# POWER_RAIL.net
KiCad netlist of a schematic drawn in Altium Designer
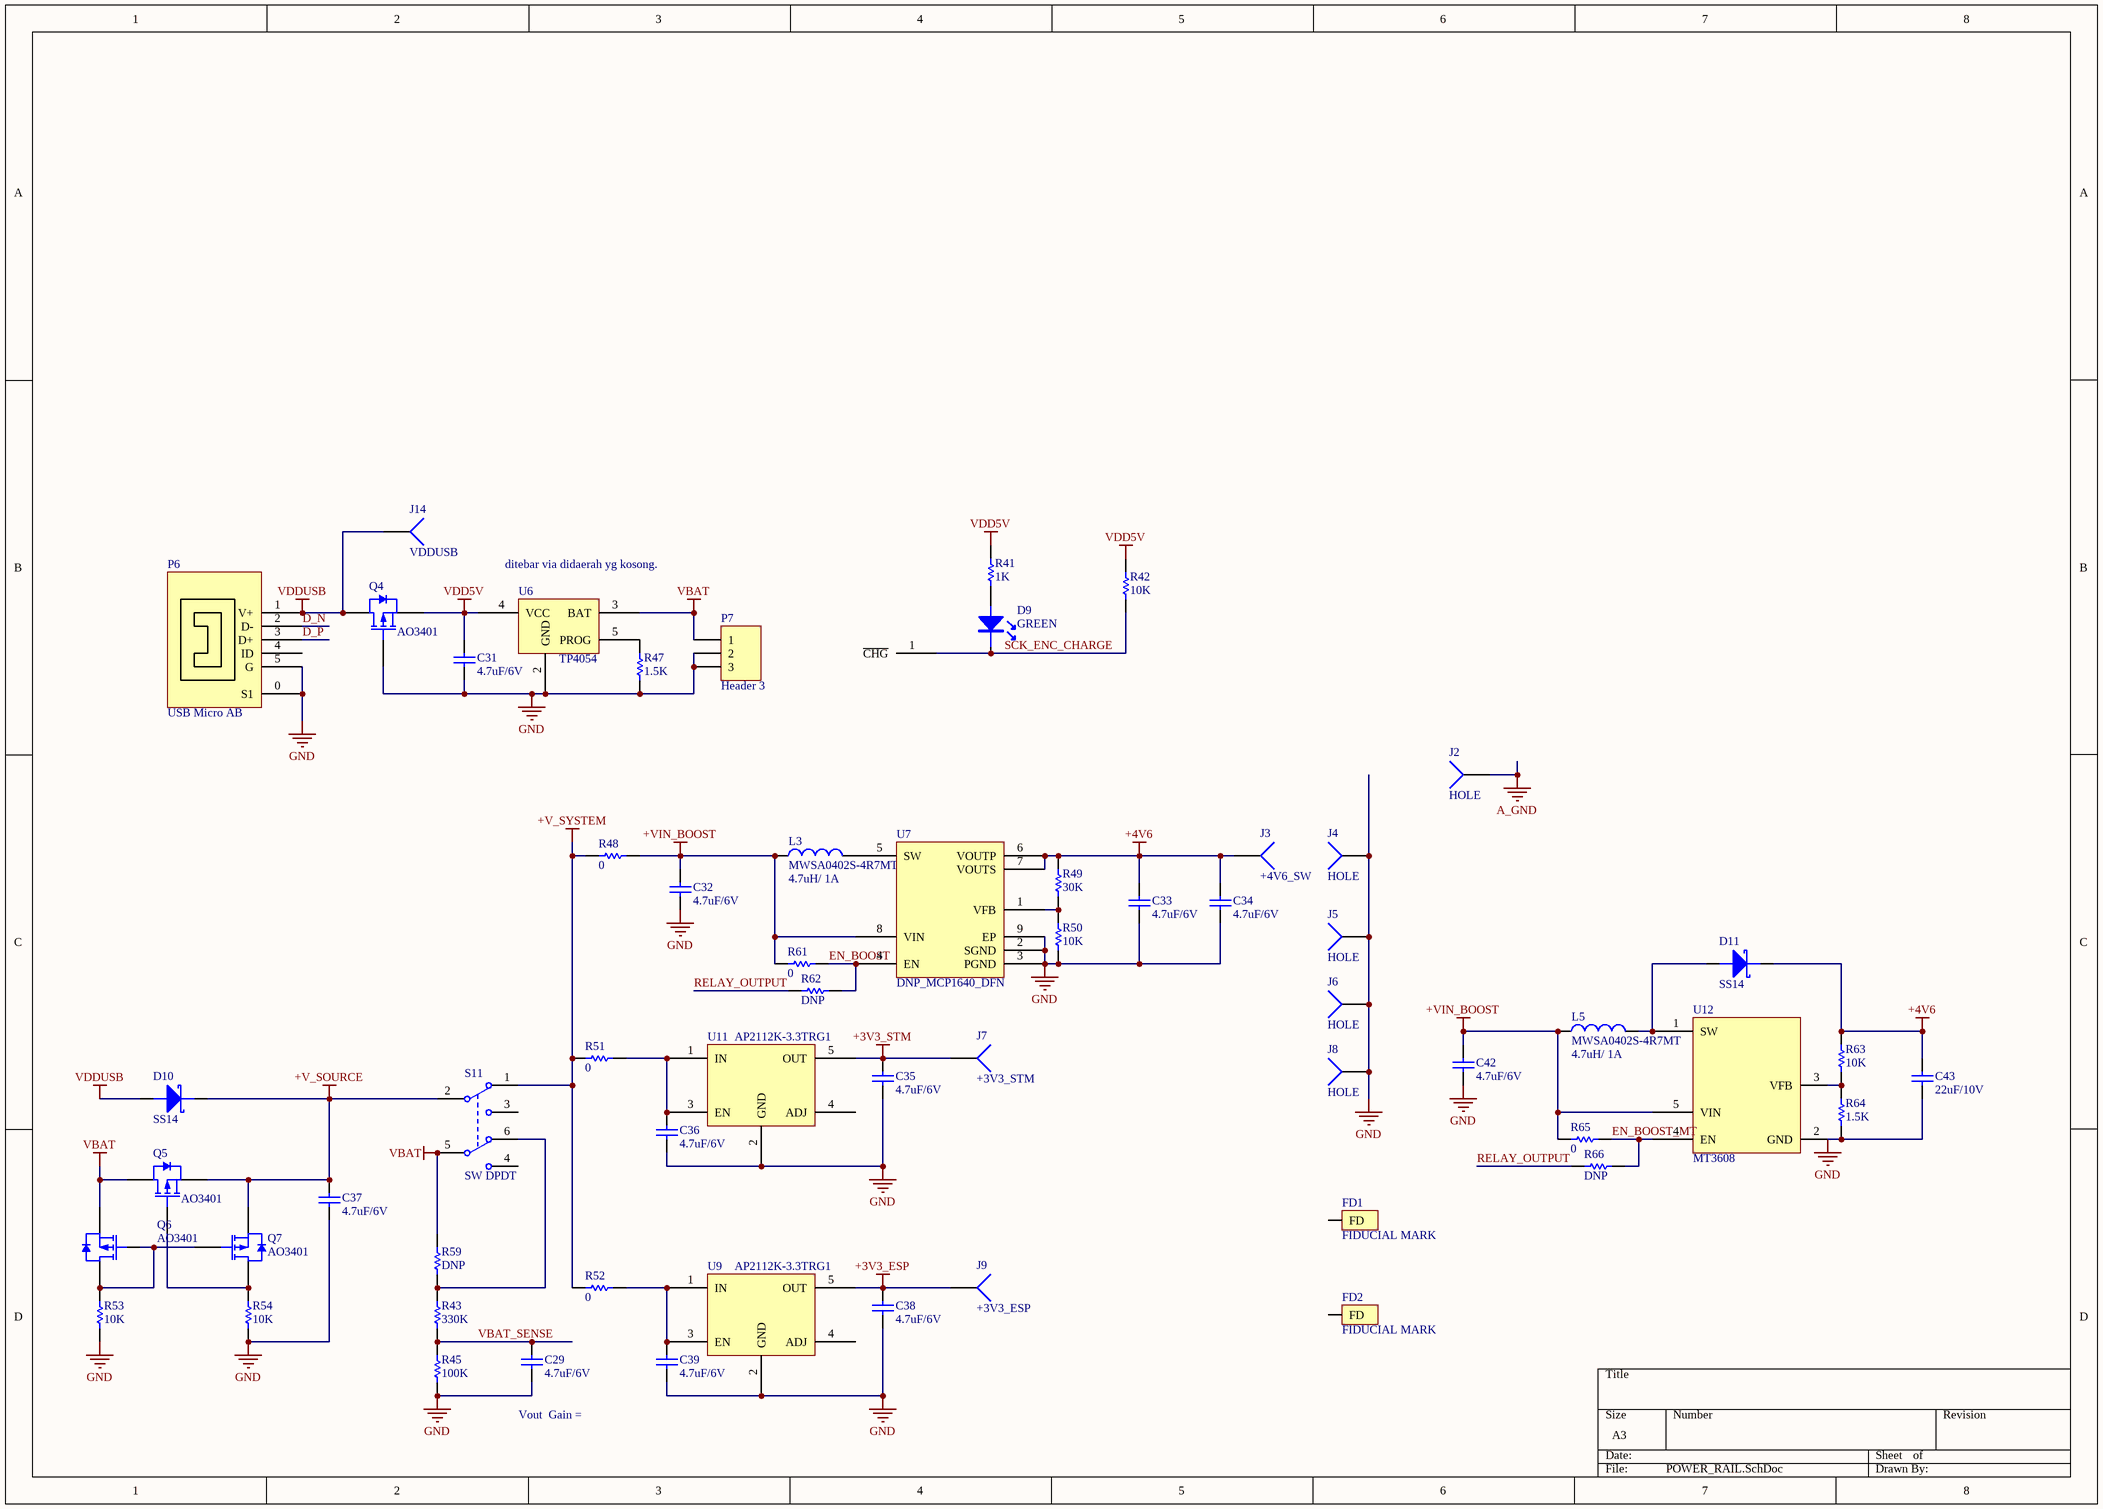
[diagram p0: POWER_RAIL.SchDoc]

(export (version "E")
  (design (tool "Eeschema 10.0.6"))
  (components
    (comp (ref "C29")
      (value "4.7uF/6V")
      (footprint "CR2012-0805")
      (description "Capacitor (Semiconductor SIM Model)")
      (fields (field (name "PUBLISHER") "Altium Limited"))
      (libsource (lib "passive") (part "Cap Semi"))
    )
    (comp (ref "C31")
      (value "4.7uF/6V")
      (footprint "CR2012-0805")
      (description "Capacitor (Semiconductor SIM Model)")
      (fields (field (name "PUBLISHER") "Altium Limited"))
      (libsource (lib "passive") (part "Cap Semi"))
    )
    (comp (ref "C32")
      (value "4.7uF/6V")
      (footprint "CR2012-0805")
      (description "Capacitor (Semiconductor SIM Model)")
      (fields (field (name "PUBLISHER") "Altium Limited"))
      (libsource (lib "passive") (part "Cap Semi"))
    )
    (comp (ref "C33")
      (value "4.7uF/6V")
      (footprint "CR2012-0805")
      (description "Capacitor (Semiconductor SIM Model)")
      (fields (field (name "PUBLISHER") "Altium Limited"))
      (libsource (lib "passive") (part "Cap Semi"))
    )
    (comp (ref "C34")
      (value "4.7uF/6V")
      (footprint "CR2012-0805")
      (description "Capacitor (Semiconductor SIM Model)")
      (fields (field (name "PUBLISHER") "Altium Limited"))
      (libsource (lib "passive") (part "Cap Semi"))
    )
    (comp (ref "C35")
      (value "4.7uF/6V")
      (footprint "CR2012-0805")
      (description "Capacitor (Semiconductor SIM Model)")
      (fields (field (name "PUBLISHER") "Altium Limited"))
      (libsource (lib "passive") (part "Cap Semi"))
    )
    (comp (ref "C36")
      (value "4.7uF/6V")
      (footprint "CR2012-0805")
      (description "Capacitor (Semiconductor SIM Model)")
      (fields (field (name "PUBLISHER") "Altium Limited"))
      (libsource (lib "passive") (part "Cap Semi"))
    )
    (comp (ref "C37")
      (value "4.7uF/6V")
      (footprint "CR2012-0805")
      (description "Capacitor (Semiconductor SIM Model)")
      (fields (field (name "PUBLISHER") "Altium Limited"))
      (libsource (lib "passive") (part "Cap Semi"))
    )
    (comp (ref "C38")
      (value "4.7uF/6V")
      (footprint "CR2012-0805")
      (description "Capacitor (Semiconductor SIM Model)")
      (fields (field (name "PUBLISHER") "Altium Limited"))
      (libsource (lib "passive") (part "Cap Semi"))
    )
    (comp (ref "C39")
      (value "4.7uF/6V")
      (footprint "CR2012-0805")
      (description "Capacitor (Semiconductor SIM Model)")
      (fields (field (name "PUBLISHER") "Altium Limited"))
      (libsource (lib "passive") (part "Cap Semi"))
    )
    (comp (ref "C42")
      (value "4.7uF/6V")
      (footprint "CR2012-0805")
      (description "Capacitor (Semiconductor SIM Model)")
      (fields (field (name "PUBLISHER") "Altium Limited"))
      (libsource (lib "passive") (part "Cap Semi"))
    )
    (comp (ref "C43")
      (value "22uF/10V")
      (footprint "CR3216-1206")
      (description "Capacitor (Semiconductor SIM Model)")
      (fields (field (name "PUBLISHER") "Altium Limited"))
      (libsource (lib "passive") (part "Cap Semi"))
    )
    (comp (ref "D9")
      (value "GREEN")
      (footprint "LED1206")
      (description "SMT LED")
      (libsource (lib "Vowstar_Basic_Device") (part "SMT_LED_0603"))
    )
    (comp (ref "D10")
      (value "SS14")
      (footprint "DO-214AC (SMA)")
      (description "Schottky Barrier Diodes")
      (fields (field (name "MANUFACTURER PART NUMBER") "SS18"))
      (libsource (lib "H2SCHALTIUM") (part "DIODE SCHOTTKY"))
    )
    (comp (ref "D11")
      (value "SS14")
      (footprint "DO-214AC (SMA)")
      (description "Schottky Barrier Diodes")
      (fields (field (name "MANUFACTURER PART NUMBER") "SS18"))
      (libsource (lib "H2SCHALTIUM") (part "DIODE SCHOTTKY"))
    )
    (comp (ref "FD1")
      (value "FIDUCIAL MARK")
      (footprint "FIDU-ROUND")
      (description "0.5mm fiducial marking with 1mm solder expansion")
      (libsource (lib "passive") (part "FIDU"))
    )
    (comp (ref "FD2")
      (value "FIDUCIAL MARK")
      (footprint "FIDU-ROUND")
      (description "0.5mm fiducial marking with 1mm solder expansion")
      (libsource (lib "passive") (part "FIDU"))
    )
    (comp (ref "J2")
      (value "HOLE")
      (footprint "HOLE_45MM")
      (description "Socket")
      (fields (field (name "PUBLISHER") "Altium Limited"))
      (libsource (lib "Miscellaneous Connectors") (part "Socket"))
    )
    (comp (ref "J3")
      (value "+4V6_SW")
      (footprint "PIN1")
      (description "Socket")
      (fields (field (name "PUBLISHER") "Altium Limited"))
      (libsource (lib "Miscellaneous Connectors") (part "Socket"))
    )
    (comp (ref "J4")
      (value "HOLE")
      (footprint "HOLE_45MM")
      (description "Socket")
      (fields (field (name "PUBLISHER") "Altium Limited"))
      (libsource (lib "Miscellaneous Connectors") (part "Socket"))
    )
    (comp (ref "J5")
      (value "HOLE")
      (footprint "HOLE_45MM")
      (description "Socket")
      (fields (field (name "PUBLISHER") "Altium Limited"))
      (libsource (lib "Miscellaneous Connectors") (part "Socket"))
    )
    (comp (ref "J6")
      (value "HOLE")
      (footprint "HOLE_45MM")
      (description "Socket")
      (fields (field (name "PUBLISHER") "Altium Limited"))
      (libsource (lib "Miscellaneous Connectors") (part "Socket"))
    )
    (comp (ref "J7")
      (value "+3V3_STM")
      (footprint "PIN1")
      (description "Socket")
      (fields (field (name "PUBLISHER") "Altium Limited"))
      (libsource (lib "Miscellaneous Connectors") (part "Socket"))
    )
    (comp (ref "J8")
      (value "HOLE")
      (footprint "HOLE_45MM")
      (description "Socket")
      (fields (field (name "PUBLISHER") "Altium Limited"))
      (libsource (lib "Miscellaneous Connectors") (part "Socket"))
    )
    (comp (ref "J9")
      (value "+3V3_ESP")
      (footprint "PIN1")
      (description "Socket")
      (fields (field (name "PUBLISHER") "Altium Limited"))
      (libsource (lib "Miscellaneous Connectors") (part "Socket"))
    )
    (comp (ref "J14")
      (value "VDDUSB")
      (footprint "PIN1")
      (description "Socket")
      (fields (field (name "PUBLISHER") "Altium Limited"))
      (libsource (lib "Miscellaneous Connectors") (part "Socket"))
    )
    (comp (ref "L3")
      (value "MWSA0402S-4R7MT")
      (footprint "IND4X4MM")
      (description "Inductor")
      (fields (field (name "ALTIUM_VALUE") "4.7uH/ 1A") (field (name "PUBLISHER") "Altium Limited"))
      (libsource (lib "passive") (part "Inductor"))
    )
    (comp (ref "L5")
      (value "MWSA0402S-4R7MT")
      (footprint "IND4X4MM")
      (description "Inductor")
      (fields (field (name "ALTIUM_VALUE") "4.7uH/ 1A") (field (name "PUBLISHER") "Altium Limited"))
      (libsource (lib "passive") (part "Inductor"))
    )
    (comp (ref "P6")
      (value "USB Micro AB")
      (footprint "USB_MICRO_wi_LEG")
      (description "USB Micro AB connector")
      (libsource (lib "passive") (part "USB Micro AB"))
    )
    (comp (ref "P7")
      (value "Header 3")
      (footprint "Molex 3p Male")
      (description "Header, 3-Pin")
      (fields (field (name "PUBLISHER") "Altium Limited"))
      (libsource (lib "Miscellaneous Connectors") (part "Header 3"))
    )
    (comp (ref "Q4")
      (value "AO3401")
      (footprint "SOT-23-3")
      (description "30V P-Channel MOSFET")
      (fields (field (name "PUBLISHER") "Altium Limited"))
      (libsource (lib "passive") (part "AO3401"))
    )
    (comp (ref "Q5")
      (value "AO3401")
      (footprint "SOT-23-3")
      (description "30V P-Channel MOSFET")
      (fields (field (name "PUBLISHER") "Altium Limited"))
      (libsource (lib "passive") (part "AO3401"))
    )
    (comp (ref "Q6")
      (value "AO3401")
      (footprint "SOT-23-3")
      (description "30V P-Channel MOSFET")
      (fields (field (name "PUBLISHER") "Altium Limited"))
      (libsource (lib "passive") (part "AO3401"))
    )
    (comp (ref "Q7")
      (value "AO3401")
      (footprint "SOT-23-3")
      (description "30V P-Channel MOSFET")
      (fields (field (name "PUBLISHER") "Altium Limited"))
      (libsource (lib "passive") (part "AO3401"))
    )
    (comp (ref "R41")
      (value "1K")
      (footprint "CR2012-0805")
      (description "Semiconductor Resistor")
      (fields (field (name "PUBLISHER") "Altium Limited"))
      (libsource (lib "passive") (part "Res Semi"))
    )
    (comp (ref "R42")
      (value "10K")
      (footprint "CR2012-0805")
      (description "Semiconductor Resistor")
      (fields (field (name "PUBLISHER") "Altium Limited"))
      (libsource (lib "passive") (part "Res Semi"))
    )
    (comp (ref "R43")
      (value "330K")
      (footprint "CR2012-0805")
      (description "Semiconductor Resistor")
      (fields (field (name "PUBLISHER") "Altium Limited"))
      (libsource (lib "passive") (part "Res Semi"))
    )
    (comp (ref "R45")
      (value "100K")
      (footprint "CR2012-0805")
      (description "Semiconductor Resistor")
      (fields (field (name "PUBLISHER") "Altium Limited"))
      (libsource (lib "passive") (part "Res Semi"))
    )
    (comp (ref "R47")
      (value "1.5K")
      (footprint "CR2012-0805")
      (description "Semiconductor Resistor")
      (fields (field (name "PUBLISHER") "Altium Limited"))
      (libsource (lib "passive") (part "Res Semi"))
    )
    (comp (ref "R48")
      (value "0")
      (footprint "JP1_SMD")
      (description "Semiconductor Resistor")
      (fields (field (name "PUBLISHER") "Altium Limited"))
      (libsource (lib "passive") (part "Res Semi"))
    )
    (comp (ref "R49")
      (value "30K")
      (footprint "CR2012-0805")
      (description "Semiconductor Resistor")
      (fields (field (name "PUBLISHER") "Altium Limited"))
      (libsource (lib "passive") (part "Res Semi"))
    )
    (comp (ref "R50")
      (value "10K")
      (footprint "CR2012-0805")
      (description "Semiconductor Resistor")
      (fields (field (name "PUBLISHER") "Altium Limited"))
      (libsource (lib "passive") (part "Res Semi"))
    )
    (comp (ref "R51")
      (value "0")
      (footprint "JP1_SMD")
      (description "Semiconductor Resistor")
      (fields (field (name "PUBLISHER") "Altium Limited"))
      (libsource (lib "passive") (part "Res Semi"))
    )
    (comp (ref "R52")
      (value "0")
      (footprint "JP1_SMD")
      (description "Semiconductor Resistor")
      (fields (field (name "PUBLISHER") "Altium Limited"))
      (libsource (lib "passive") (part "Res Semi"))
    )
    (comp (ref "R53")
      (value "10K")
      (footprint "CR2012-0805")
      (description "Semiconductor Resistor")
      (fields (field (name "PUBLISHER") "Altium Limited"))
      (libsource (lib "passive") (part "Res Semi"))
    )
    (comp (ref "R54")
      (value "10K")
      (footprint "CR2012-0805")
      (description "Semiconductor Resistor")
      (fields (field (name "PUBLISHER") "Altium Limited"))
      (libsource (lib "passive") (part "Res Semi"))
    )
    (comp (ref "R59")
      (value "DNP")
      (footprint "JP1_SMD")
      (description "Semiconductor Resistor")
      (fields (field (name "PUBLISHER") "Altium Limited"))
      (libsource (lib "passive") (part "Res Semi"))
    )
    (comp (ref "R61")
      (value "0")
      (footprint "JP1_SMD")
      (description "Semiconductor Resistor")
      (fields (field (name "PUBLISHER") "Altium Limited"))
      (libsource (lib "passive") (part "Res Semi"))
    )
    (comp (ref "R62")
      (value "DNP")
      (footprint "JP1_SMD")
      (description "Semiconductor Resistor")
      (fields (field (name "PUBLISHER") "Altium Limited"))
      (libsource (lib "passive") (part "Res Semi"))
    )
    (comp (ref "R63")
      (value "10K")
      (footprint "CR2012-0805")
      (description "Semiconductor Resistor")
      (fields (field (name "PUBLISHER") "Altium Limited"))
      (libsource (lib "passive") (part "Res Semi"))
    )
    (comp (ref "R64")
      (value "1.5K")
      (footprint "CR2012-0805")
      (description "Semiconductor Resistor")
      (fields (field (name "PUBLISHER") "Altium Limited"))
      (libsource (lib "passive") (part "Res Semi"))
    )
    (comp (ref "R65")
      (value "0")
      (footprint "JP1_SMD")
      (description "Semiconductor Resistor")
      (fields (field (name "PUBLISHER") "Altium Limited"))
      (libsource (lib "passive") (part "Res Semi"))
    )
    (comp (ref "R66")
      (value "DNP")
      (footprint "JP1_SMD")
      (description "Semiconductor Resistor")
      (fields (field (name "PUBLISHER") "Altium Limited"))
      (libsource (lib "passive") (part "Res Semi"))
    )
    (comp (ref "S11")
      (value "SW DPDT")
      (footprint "SWITCH_SPDT")
      (description "Switch")
      (fields (field (name "PUBLISHER") "Altium Limited"))
      (libsource (lib "passive") (part "SW DPDT"))
    )
    (comp (ref "U6") (value "TP4054") (footprint "SOT23-5") (libsource (lib "TP4056") (part "TP4056")))
    (comp (ref "U7")
      (value "DNP_MCP1640_DFN")
      (footprint "DFN-8_2X3")
      (description "Synchronous Boost Regulator with True Output Disconnect or Input/Output Bypass Option")
      (libsource (lib "active") (part "MCP1640_DFN"))
    )
    (comp (ref "U9")
      (value "AP2112K-3.3TRG1")
      (footprint "SOT-23-5")
      (description "IC REG LDO ADJ .15A SOT25-5")
      (fields
        (field (name "MANUFACTURER") "Diodes Inc")
        (field (name "SUPPLIER PART NUMBER") "AP2112K-3.3TRG1")
        (field (name "MANUFACTURER PART NUMBER") "AP7311-18WG-7")
      )
      (libsource (lib "active") (part "AP7311"))
    )
    (comp (ref "U11")
      (value "AP2112K-3.3TRG1")
      (footprint "SOT-23-5")
      (description "IC REG LDO ADJ .15A SOT25-5")
      (fields
        (field (name "MANUFACTURER") "Diodes Inc")
        (field (name "SUPPLIER PART NUMBER") "AP2112K-3.3TRG1")
        (field (name "MANUFACTURER PART NUMBER") "AP7311-18WG-7")
      )
      (libsource (lib "active") (part "AP7311"))
    )
    (comp (ref "U12")
      (value "MT3608")
      (footprint "SOT-23-6")
      (description "Synchronous Boost Regulator with True Output Disconnect or Input/Output Bypass Option")
      (libsource (lib "active") (part "MT3608"))
    )
  )
  (nets
    (net (code "1") (name "+3V3_ESP") (class "Default")
      (node (ref "C38") (pin "2") (pinfunction "2_2") (pintype "passive"))
      (node (ref "J9") (pin "1") (pinfunction "1_1") (pintype "passive"))
      (node (ref "U9") (pin "5") (pinfunction "OUT_5") (pintype "passive"))
    )
    (net (code "2") (name "+3V3_STM") (class "Default")
      (node (ref "C35") (pin "2") (pinfunction "2_2") (pintype "passive"))
      (node (ref "J7") (pin "1") (pinfunction "1_1") (pintype "passive"))
      (node (ref "U11") (pin "5") (pinfunction "OUT_5") (pintype "passive"))
    )
    (net (code "3") (name "+4V6") (class "Default")
      (node (ref "C33") (pin "2") (pinfunction "2_2") (pintype "passive"))
      (node (ref "C34") (pin "2") (pinfunction "2_2") (pintype "passive"))
      (node (ref "C43") (pin "2") (pinfunction "2_2") (pintype "passive"))
      (node (ref "D11") (pin "2") (pinfunction "K_2") (pintype "passive"))
      (node (ref "J3") (pin "1") (pinfunction "1_1") (pintype "passive"))
      (node (ref "R49") (pin "2") (pinfunction "2_2") (pintype "passive"))
      (node (ref "R63") (pin "2") (pinfunction "2_2") (pintype "passive"))
      (node (ref "U7") (pin "6") (pinfunction "VOUTP_6") (pintype "passive"))
      (node (ref "U7") (pin "7") (pinfunction "VOUTS_7") (pintype "passive"))
    )
    (net (code "4") (name "+VIN_BOOST") (class "Default")
      (node (ref "C32") (pin "2") (pinfunction "2_2") (pintype "passive"))
      (node (ref "C42") (pin "2") (pinfunction "2_2") (pintype "passive"))
      (node (ref "L3") (pin "1") (pinfunction "1_1") (pintype "passive"))
      (node (ref "L5") (pin "1") (pinfunction "1_1") (pintype "passive"))
      (node (ref "R48") (pin "2") (pinfunction "2_2") (pintype "passive"))
      (node (ref "R61") (pin "1") (pinfunction "1_1") (pintype "passive"))
      (node (ref "R65") (pin "1") (pinfunction "1_1") (pintype "passive"))
      (node (ref "U12") (pin "5") (pinfunction "VIN_5") (pintype "passive"))
      (node (ref "U7") (pin "8") (pinfunction "VIN_8") (pintype "passive"))
    )
    (net (code "5") (name "+V_SOURCE") (class "Default")
      (node (ref "C37") (pin "2") (pinfunction "2_2") (pintype "passive"))
      (node (ref "D10") (pin "2") (pinfunction "K_2") (pintype "passive"))
      (node (ref "Q5") (pin "2") (pinfunction "S_2") (pintype "passive"))
      (node (ref "Q7") (pin "2") (pinfunction "S_2") (pintype "passive"))
      (node (ref "S11") (pin "2") (pinfunction "COMMON1_2") (pintype "passive"))
    )
    (net (code "6") (name "+V_SYSTEM") (class "Default")
      (node (ref "R48") (pin "1") (pinfunction "1_1") (pintype "passive"))
      (node (ref "R51") (pin "1") (pinfunction "1_1") (pintype "passive"))
      (node (ref "R52") (pin "1") (pinfunction "1_1") (pintype "passive"))
      (node (ref "S11") (pin "1") (pinfunction "NC1_1") (pintype "passive"))
    )
    (net (code "7") (name "/D_N") (class "Default")
      (node (ref "P6") (pin "2") (pinfunction "D-_2") (pintype "passive"))
    )
    (net (code "8") (name "/D_P") (class "Default")
      (node (ref "P6") (pin "3") (pinfunction "D+_3") (pintype "passive"))
    )
    (net (code "9") (name "/EN_BOOST") (class "Default")
      (node (ref "R61") (pin "2") (pinfunction "2_2") (pintype "passive"))
      (node (ref "R62") (pin "1") (pinfunction "1_1") (pintype "passive"))
      (node (ref "U7") (pin "4") (pinfunction "EN_4") (pintype "passive"))
    )
    (net (code "10") (name "/EN_BOOST_MT") (class "Default")
      (node (ref "R65") (pin "2") (pinfunction "2_2") (pintype "passive"))
      (node (ref "R66") (pin "1") (pinfunction "1_1") (pintype "passive"))
      (node (ref "U12") (pin "4") (pinfunction "EN_4") (pintype "passive"))
    )
    (net (code "11") (name "/RELAY_OUTPUT") (class "Default")
      (node (ref "R62") (pin "2") (pinfunction "2_2") (pintype "passive"))
      (node (ref "R66") (pin "2") (pinfunction "2_2") (pintype "passive"))
    )
    (net (code "12") (name "/SCK_ENC_CHARGE") (class "Default")
      (node (ref "D9") (pin "K") (pinfunction "K_K") (pintype "passive"))
      (node (ref "R42") (pin "1") (pinfunction "1_1") (pintype "passive"))
      (node (ref "U6") (pin "1") (pinfunction "~{CHG}_1") (pintype "passive"))
    )
    (net (code "13") (name "/VBAT_SENSE") (class "Default")
      (node (ref "C29") (pin "2") (pinfunction "2_2") (pintype "passive"))
      (node (ref "R43") (pin "1") (pinfunction "1_1") (pintype "passive"))
      (node (ref "R45") (pin "2") (pinfunction "2_2") (pintype "passive"))
    )
    (net (code "14") (name "A_GND") (class "Default")
      (node (ref "J2") (pin "1") (pinfunction "1_1") (pintype "passive"))
    )
    (net (code "15") (name "GND") (class "Default")
      (node (ref "C29") (pin "1") (pinfunction "1_1") (pintype "passive"))
      (node (ref "C31") (pin "1") (pinfunction "1_1") (pintype "passive"))
      (node (ref "C32") (pin "1") (pinfunction "1_1") (pintype "passive"))
      (node (ref "C33") (pin "1") (pinfunction "1_1") (pintype "passive"))
      (node (ref "C34") (pin "1") (pinfunction "1_1") (pintype "passive"))
      (node (ref "C35") (pin "1") (pinfunction "1_1") (pintype "passive"))
      (node (ref "C36") (pin "1") (pinfunction "1_1") (pintype "passive"))
      (node (ref "C37") (pin "1") (pinfunction "1_1") (pintype "passive"))
      (node (ref "C38") (pin "1") (pinfunction "1_1") (pintype "passive"))
      (node (ref "C39") (pin "1") (pinfunction "1_1") (pintype "passive"))
      (node (ref "C42") (pin "1") (pinfunction "1_1") (pintype "passive"))
      (node (ref "C43") (pin "1") (pinfunction "1_1") (pintype "passive"))
      (node (ref "J4") (pin "1") (pinfunction "1_1") (pintype "passive"))
      (node (ref "J5") (pin "1") (pinfunction "1_1") (pintype "passive"))
      (node (ref "J6") (pin "1") (pinfunction "1_1") (pintype "passive"))
      (node (ref "J8") (pin "1") (pinfunction "1_1") (pintype "passive"))
      (node (ref "P6") (pin "0") (pinfunction "S1_0") (pintype "passive"))
      (node (ref "P6") (pin "5") (pinfunction "G_5") (pintype "passive"))
      (node (ref "P7") (pin "2") (pinfunction "2_2") (pintype "passive"))
      (node (ref "P7") (pin "3") (pinfunction "3_3") (pintype "passive"))
      (node (ref "Q4") (pin "1") (pinfunction "G_1") (pintype "passive"))
      (node (ref "R45") (pin "1") (pinfunction "1_1") (pintype "passive"))
      (node (ref "R47") (pin "1") (pinfunction "1_1") (pintype "passive"))
      (node (ref "R50") (pin "1") (pinfunction "1_1") (pintype "passive"))
      (node (ref "R53") (pin "1") (pinfunction "1_1") (pintype "passive"))
      (node (ref "R54") (pin "1") (pinfunction "1_1") (pintype "passive"))
      (node (ref "R64") (pin "1") (pinfunction "1_1") (pintype "passive"))
      (node (ref "U11") (pin "2") (pinfunction "GND_2") (pintype "passive"))
      (node (ref "U12") (pin "2") (pinfunction "GND_2") (pintype "passive"))
      (node (ref "U6") (pin "2") (pinfunction "GND_2") (pintype "passive"))
      (node (ref "U7") (pin "2") (pinfunction "SGND_2") (pintype "passive"))
      (node (ref "U7") (pin "3") (pinfunction "PGND_3") (pintype "passive"))
      (node (ref "U7") (pin "9") (pinfunction "EP_9") (pintype "passive"))
      (node (ref "U9") (pin "2") (pinfunction "GND_2") (pintype "passive"))
    )
    (net (code "16") (name "Net-(D9-PadA)") (class "Default")
      (node (ref "D9") (pin "A") (pinfunction "A_A") (pintype "passive"))
      (node (ref "R41") (pin "1") (pinfunction "1_1") (pintype "passive"))
    )
    (net (code "17") (name "Net-(D11-A)") (class "Default")
      (node (ref "D11") (pin "1") (pinfunction "A_1") (pintype "passive"))
      (node (ref "L5") (pin "2") (pinfunction "2_2") (pintype "passive"))
      (node (ref "U12") (pin "1") (pinfunction "SW_1") (pintype "passive"))
    )
    (net (code "18") (name "Net-(Q5-G)") (class "Default")
      (node (ref "Q5") (pin "1") (pinfunction "G_1") (pintype "passive"))
      (node (ref "Q7") (pin "3") (pinfunction "D_3") (pintype "passive"))
      (node (ref "R54") (pin "2") (pinfunction "2_2") (pintype "passive"))
    )
    (net (code "19") (name "Net-(Q6-D)") (class "Default")
      (node (ref "Q6") (pin "1") (pinfunction "G_1") (pintype "passive"))
      (node (ref "Q6") (pin "3") (pinfunction "D_3") (pintype "passive"))
      (node (ref "Q7") (pin "1") (pinfunction "G_1") (pintype "passive"))
      (node (ref "R53") (pin "2") (pinfunction "2_2") (pintype "passive"))
    )
    (net (code "20") (name "Net-(S11-NO2)") (class "Default")
      (node (ref "R43") (pin "2") (pinfunction "2_2") (pintype "passive"))
      (node (ref "R59") (pin "1") (pinfunction "1_1") (pintype "passive"))
      (node (ref "S11") (pin "6") (pinfunction "NO2_6") (pintype "passive"))
    )
    (net (code "21") (name "Net-(U6-PROG)") (class "Default")
      (node (ref "R47") (pin "2") (pinfunction "2_2") (pintype "passive"))
      (node (ref "U6") (pin "5") (pinfunction "PROG_5") (pintype "passive"))
    )
    (net (code "22") (name "Net-(U7-SW)") (class "Default")
      (node (ref "L3") (pin "2") (pinfunction "2_2") (pintype "passive"))
      (node (ref "U7") (pin "5") (pinfunction "SW_5") (pintype "passive"))
    )
    (net (code "23") (name "Net-(U7-VFB)") (class "Default")
      (node (ref "R49") (pin "1") (pinfunction "1_1") (pintype "passive"))
      (node (ref "R50") (pin "2") (pinfunction "2_2") (pintype "passive"))
      (node (ref "U7") (pin "1") (pinfunction "VFB_1") (pintype "passive"))
    )
    (net (code "24") (name "Net-(U9-EN)") (class "Default")
      (node (ref "C39") (pin "2") (pinfunction "2_2") (pintype "passive"))
      (node (ref "R52") (pin "2") (pinfunction "2_2") (pintype "passive"))
      (node (ref "U9") (pin "1") (pinfunction "IN_1") (pintype "passive"))
      (node (ref "U9") (pin "3") (pinfunction "EN_3") (pintype "passive"))
    )
    (net (code "25") (name "Net-(U11-EN)") (class "Default")
      (node (ref "C36") (pin "2") (pinfunction "2_2") (pintype "passive"))
      (node (ref "R51") (pin "2") (pinfunction "2_2") (pintype "passive"))
      (node (ref "U11") (pin "1") (pinfunction "IN_1") (pintype "passive"))
      (node (ref "U11") (pin "3") (pinfunction "EN_3") (pintype "passive"))
    )
    (net (code "26") (name "Net-(U12-VFB)") (class "Default")
      (node (ref "R63") (pin "1") (pinfunction "1_1") (pintype "passive"))
      (node (ref "R64") (pin "2") (pinfunction "2_2") (pintype "passive"))
      (node (ref "U12") (pin "3") (pinfunction "VFB_3") (pintype "passive"))
    )
    (net (code "27") (name "VBAT") (class "Default")
      (node (ref "P7") (pin "1") (pinfunction "1_1") (pintype "passive"))
      (node (ref "Q5") (pin "3") (pinfunction "D_3") (pintype "passive"))
      (node (ref "Q6") (pin "2") (pinfunction "S_2") (pintype "passive"))
      (node (ref "R59") (pin "2") (pinfunction "2_2") (pintype "passive"))
      (node (ref "S11") (pin "5") (pinfunction "COMMON2_5") (pintype "passive"))
      (node (ref "U6") (pin "3") (pinfunction "BAT_3") (pintype "passive"))
    )
    (net (code "28") (name "VDD5V") (class "Default")
      (node (ref "C31") (pin "2") (pinfunction "2_2") (pintype "passive"))
      (node (ref "Q4") (pin "2") (pinfunction "S_2") (pintype "passive"))
      (node (ref "R41") (pin "2") (pinfunction "2_2") (pintype "passive"))
      (node (ref "R42") (pin "2") (pinfunction "2_2") (pintype "passive"))
      (node (ref "U6") (pin "4") (pinfunction "VCC_4") (pintype "passive"))
    )
    (net (code "29") (name "VDDUSB") (class "Default")
      (node (ref "D10") (pin "1") (pinfunction "A_1") (pintype "passive"))
      (node (ref "J14") (pin "1") (pinfunction "1_1") (pintype "passive"))
      (node (ref "P6") (pin "1") (pinfunction "V+_1") (pintype "passive"))
      (node (ref "Q4") (pin "3") (pinfunction "D_3") (pintype "passive"))
    )
    (net (code "30") (name "unconnected-(FD1-FD-Pad1)") (class "Default")
      (node (ref "FD1") (pin "1") (pinfunction "FD_1") (pintype "passive"))
    )
    (net (code "31") (name "unconnected-(FD2-FD-Pad1)") (class "Default")
      (node (ref "FD2") (pin "1") (pinfunction "FD_1") (pintype "passive"))
    )
    (net (code "32") (name "unconnected-(P6-ID-Pad4)") (class "Default")
      (node (ref "P6") (pin "4") (pinfunction "ID_4") (pintype "passive"))
    )
    (net (code "33") (name "unconnected-(S11-NC2-Pad4)") (class "Default")
      (node (ref "S11") (pin "4") (pinfunction "NC2_4") (pintype "passive"))
    )
    (net (code "34") (name "unconnected-(S11-NO1-Pad3)") (class "Default")
      (node (ref "S11") (pin "3") (pinfunction "NO1_3") (pintype "passive"))
    )
    (net (code "35") (name "unconnected-(U9-ADJ-Pad4)") (class "Default")
      (node (ref "U9") (pin "4") (pinfunction "ADJ_4") (pintype "passive"))
    )
    (net (code "36") (name "unconnected-(U11-ADJ-Pad4)") (class "Default")
      (node (ref "U11") (pin "4") (pinfunction "ADJ_4") (pintype "passive"))
    )
  )
)
